# RP2040.net
KiCad netlist of a schematic drawn in Altium Designer
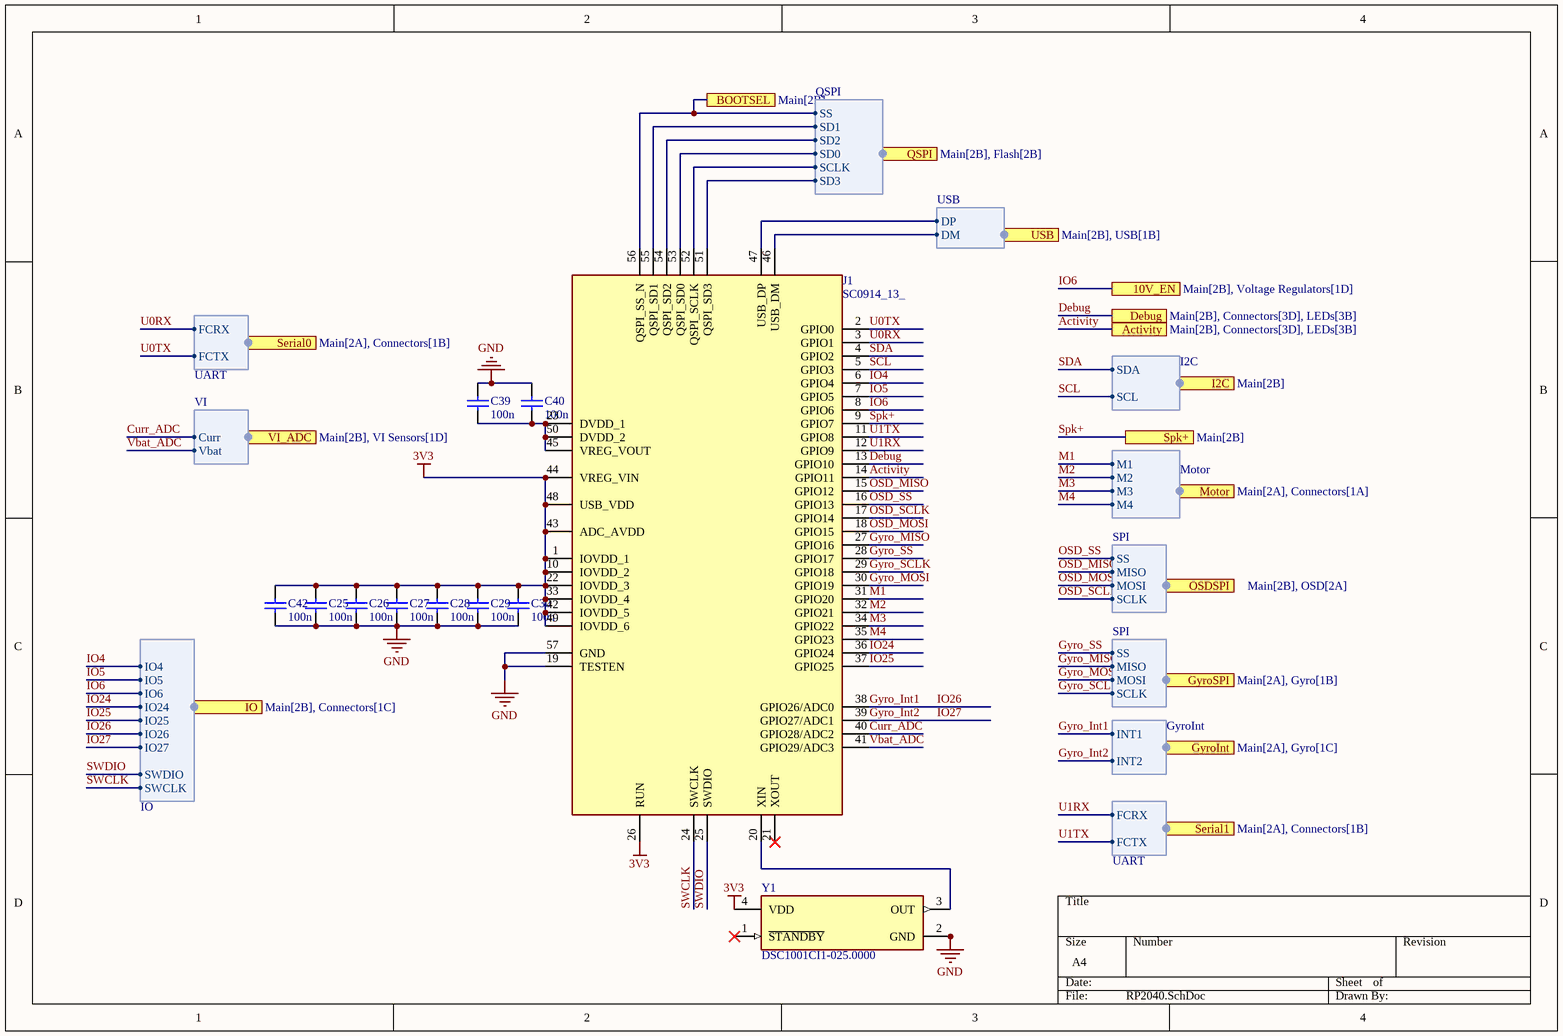
[diagram p0: RP2040.SchDoc]

(export (version "E")
  (design (tool "Eeschema 10.0.6"))
  (components
    (comp (ref "C25")
      (value "100n")
      (footprint "CAPC0603(1608)55_N")
      (description "Keramikvielschichtkondensator, SMD, Baureihe MC, ± 20%")
      (fields (field (name "MANUFACTURER") "Multicomp"))
      (libsource (lib "Standardbauteile") (part "Cap 100n"))
    )
    (comp (ref "C26")
      (value "100n")
      (footprint "CAPC0603(1608)55_N")
      (description "Keramikvielschichtkondensator, SMD, Baureihe MC, ± 20%")
      (fields (field (name "MANUFACTURER") "Multicomp"))
      (libsource (lib "Standardbauteile") (part "Cap 100n"))
    )
    (comp (ref "C27")
      (value "100n")
      (footprint "CAPC0603(1608)55_N")
      (description "Keramikvielschichtkondensator, SMD, Baureihe MC, ± 20%")
      (fields (field (name "MANUFACTURER") "Multicomp"))
      (libsource (lib "Standardbauteile") (part "Cap 100n"))
    )
    (comp (ref "C28")
      (value "100n")
      (footprint "CAPC0603(1608)55_N")
      (description "Keramikvielschichtkondensator, SMD, Baureihe MC, ± 20%")
      (fields (field (name "MANUFACTURER") "Multicomp"))
      (libsource (lib "Standardbauteile") (part "Cap 100n"))
    )
    (comp (ref "C29")
      (value "100n")
      (footprint "CAPC0603(1608)55_N")
      (description "Keramikvielschichtkondensator, SMD, Baureihe MC, ± 20%")
      (fields (field (name "MANUFACTURER") "Multicomp"))
      (libsource (lib "Standardbauteile") (part "Cap 100n"))
    )
    (comp (ref "C30")
      (value "100n")
      (footprint "CAPC0603(1608)55_N")
      (description "Keramikvielschichtkondensator, SMD, Baureihe MC, ± 20%")
      (fields (field (name "MANUFACTURER") "Multicomp"))
      (libsource (lib "Standardbauteile") (part "Cap 100n"))
    )
    (comp (ref "C39")
      (value "100n")
      (footprint "CAPC0603(1608)55_N")
      (description "Keramikvielschichtkondensator, SMD, Baureihe MC, ± 20%")
      (fields (field (name "MANUFACTURER") "Multicomp"))
      (libsource (lib "Standardbauteile") (part "Cap 100n"))
    )
    (comp (ref "C40")
      (value "100n")
      (footprint "CAPC0603(1608)55_N")
      (description "Keramikvielschichtkondensator, SMD, Baureihe MC, ± 20%")
      (fields (field (name "MANUFACTURER") "Multicomp"))
      (libsource (lib "Standardbauteile") (part "Cap 100n"))
    )
    (comp (ref "C42")
      (value "100n")
      (footprint "CAPC0603(1608)55_N")
      (description "Keramikvielschichtkondensator, SMD, Baureihe MC, ± 20%")
      (fields (field (name "MANUFACTURER") "Multicomp"))
      (libsource (lib "Standardbauteile") (part "Cap 100n"))
    )
    (comp (ref "J1")
      (value "SC0914_13_")
      (footprint "Custom Components:SC091413")
      (description "Connector")
      (fields
        (field (name "MANUFACTURER_PART_NUMBER") "SC0914(13)")
        (field (name "MOUSER PART NUMBER") "358-SC091413")
      )
      (libsource (lib "Custom Components") (part "SC0914_13_"))
    )
    (comp (ref "Y1")
      (value "DSC1001CI1-025.0000")
      (footprint "FP-CDFN3225-4LD-PL-1-MFG")
      (description "MEMS OSC XO 25.0000MHZ CMOS SMD")
      (libsource (lib "Altium Content Vault") (part "8720c5899389794f50cb41edc4e4c8a"))
    )
  )
  (nets
    (net (code "10") (name "/Activity") (class "Default")
      (node (ref "J1") (pin "14") (pinfunction "GPIO11_14") (pintype "passive"))
    )
    (net (code "11") (name "/BOOTSEL") (class "Default")
      (node (ref "J1") (pin "56") (pinfunction "QSPI_SS_N_56") (pintype "passive"))
    )
    (net (code "12") (name "/Curr_ADC") (class "Default")
      (node (ref "J1") (pin "40") (pinfunction "GPIO28/ADC2_40") (pintype "passive"))
    )
    (net (code "13") (name "/DM") (class "Default")
      (node (ref "J1") (pin "46") (pinfunction "USB_DM_46") (pintype "passive"))
    )
    (net (code "14") (name "/DP") (class "Default")
      (node (ref "J1") (pin "47") (pinfunction "USB_DP_47") (pintype "passive"))
    )
    (net (code "15") (name "/Debug") (class "Default")
      (node (ref "J1") (pin "13") (pinfunction "GPIO10_13") (pintype "passive"))
    )
    (net (code "16") (name "/Gyro_Int1") (class "Default")
      (node (ref "J1") (pin "38") (pinfunction "GPIO26/ADC0_38") (pintype "passive"))
    )
    (net (code "17") (name "/Gyro_Int2") (class "Default")
      (node (ref "J1") (pin "39") (pinfunction "GPIO27/ADC1_39") (pintype "passive"))
    )
    (net (code "18") (name "/Gyro_MISO") (class "Default")
      (node (ref "J1") (pin "27") (pinfunction "GPIO16_27") (pintype "passive"))
    )
    (net (code "19") (name "/Gyro_MOSI") (class "Default")
      (node (ref "J1") (pin "30") (pinfunction "GPIO19_30") (pintype "passive"))
    )
    (net (code "20") (name "/Gyro_SCLK") (class "Default")
      (node (ref "J1") (pin "29") (pinfunction "GPIO18_29") (pintype "passive"))
    )
    (net (code "21") (name "/Gyro_SS") (class "Default")
      (node (ref "J1") (pin "28") (pinfunction "GPIO17_28") (pintype "passive"))
    )
    (net (code "22") (name "/IO4") (class "Default")
      (node (ref "J1") (pin "6") (pinfunction "GPIO4_6") (pintype "passive"))
    )
    (net (code "23") (name "/IO5") (class "Default")
      (node (ref "J1") (pin "7") (pinfunction "GPIO5_7") (pintype "passive"))
    )
    (net (code "24") (name "/IO6") (class "Default")
      (node (ref "J1") (pin "8") (pinfunction "GPIO6_8") (pintype "passive"))
    )
    (net (code "25") (name "/IO24") (class "Default")
      (node (ref "J1") (pin "36") (pinfunction "GPIO24_36") (pintype "passive"))
    )
    (net (code "26") (name "/IO25") (class "Default")
      (node (ref "J1") (pin "37") (pinfunction "GPIO25_37") (pintype "passive"))
    )
    (net (code "27") (name "/M1") (class "Default")
      (node (ref "J1") (pin "31") (pinfunction "GPIO20_31") (pintype "passive"))
    )
    (net (code "28") (name "/M2") (class "Default")
      (node (ref "J1") (pin "32") (pinfunction "GPIO21_32") (pintype "passive"))
    )
    (net (code "29") (name "/M3") (class "Default")
      (node (ref "J1") (pin "34") (pinfunction "GPIO22_34") (pintype "passive"))
    )
    (net (code "30") (name "/M4") (class "Default")
      (node (ref "J1") (pin "35") (pinfunction "GPIO23_35") (pintype "passive"))
    )
    (net (code "31") (name "/OSD_MISO") (class "Default")
      (node (ref "J1") (pin "15") (pinfunction "GPIO12_15") (pintype "passive"))
    )
    (net (code "32") (name "/OSD_MOSI") (class "Default")
      (node (ref "J1") (pin "18") (pinfunction "GPIO15_18") (pintype "passive"))
    )
    (net (code "33") (name "/OSD_SCLK") (class "Default")
      (node (ref "J1") (pin "17") (pinfunction "GPIO14_17") (pintype "passive"))
    )
    (net (code "34") (name "/OSD_SS") (class "Default")
      (node (ref "J1") (pin "16") (pinfunction "GPIO13_16") (pintype "passive"))
    )
    (net (code "35") (name "/SCL") (class "Default")
      (node (ref "J1") (pin "5") (pinfunction "GPIO3_5") (pintype "passive"))
    )
    (net (code "36") (name "/SD0") (class "Default")
      (node (ref "J1") (pin "53") (pinfunction "QSPI_SD0_53") (pintype "passive"))
    )
    (net (code "37") (name "/SD1") (class "Default")
      (node (ref "J1") (pin "55") (pinfunction "QSPI_SD1_55") (pintype "passive"))
    )
    (net (code "38") (name "/SD2") (class "Default")
      (node (ref "J1") (pin "54") (pinfunction "QSPI_SD2_54") (pintype "passive"))
    )
    (net (code "39") (name "/SD3") (class "Default")
      (node (ref "J1") (pin "51") (pinfunction "QSPI_SD3_51") (pintype "passive"))
    )
    (net (code "40") (name "/SDA") (class "Default")
      (node (ref "J1") (pin "4") (pinfunction "GPIO2_4") (pintype "passive"))
    )
    (net (code "41") (name "/SWCLK") (class "Default")
      (node (ref "J1") (pin "24") (pinfunction "SWCLK_24") (pintype "passive"))
    )
    (net (code "42") (name "/SWDIO") (class "Default")
      (node (ref "J1") (pin "25") (pinfunction "SWDIO_25") (pintype "passive"))
    )
    (net (code "43") (name "/Spk+") (class "Default")
      (node (ref "J1") (pin "9") (pinfunction "GPIO7_9") (pintype "passive"))
    )
    (net (code "44") (name "/U0RX") (class "Default")
      (node (ref "J1") (pin "3") (pinfunction "GPIO1_3") (pintype "passive"))
    )
    (net (code "45") (name "/U0TX") (class "Default")
      (node (ref "J1") (pin "2") (pinfunction "GPIO0_2") (pintype "passive"))
    )
    (net (code "46") (name "/U1RX") (class "Default")
      (node (ref "J1") (pin "12") (pinfunction "GPIO9_12") (pintype "passive"))
    )
    (net (code "47") (name "/U1TX") (class "Default")
      (node (ref "J1") (pin "11") (pinfunction "GPIO8_11") (pintype "passive"))
    )
    (net (code "48") (name "/Vbat_ADC") (class "Default")
      (node (ref "J1") (pin "41") (pinfunction "GPIO29/ADC3_41") (pintype "passive"))
    )
    (net (code "58") (name "3V3") (class "Default")
      (node (ref "C25") (pin "2") (pinfunction "2_2") (pintype "passive"))
      (node (ref "C26") (pin "2") (pinfunction "2_2") (pintype "passive"))
      (node (ref "C27") (pin "2") (pinfunction "2_2") (pintype "passive"))
      (node (ref "C28") (pin "2") (pinfunction "2_2") (pintype "passive"))
      (node (ref "C29") (pin "2") (pinfunction "2_2") (pintype "passive"))
      (node (ref "C30") (pin "2") (pinfunction "2_2") (pintype "passive"))
      (node (ref "C42") (pin "2") (pinfunction "2_2") (pintype "passive"))
      (node (ref "J1") (pin "1") (pinfunction "IOVDD_1_1") (pintype "passive"))
      (node (ref "J1") (pin "10") (pinfunction "IOVDD_2_10") (pintype "passive"))
      (node (ref "J1") (pin "22") (pinfunction "IOVDD_3_22") (pintype "passive"))
      (node (ref "J1") (pin "26") (pinfunction "RUN_26") (pintype "passive"))
      (node (ref "J1") (pin "33") (pinfunction "IOVDD_4_33") (pintype "passive"))
      (node (ref "J1") (pin "42") (pinfunction "IOVDD_5_42") (pintype "passive"))
      (node (ref "J1") (pin "43") (pinfunction "ADC_AVDD_43") (pintype "passive"))
      (node (ref "J1") (pin "44") (pinfunction "VREG_VIN_44") (pintype "passive"))
      (node (ref "J1") (pin "48") (pinfunction "USB_VDD_48") (pintype "passive"))
      (node (ref "J1") (pin "49") (pinfunction "IOVDD_6_49") (pintype "passive"))
      (node (ref "Y1") (pin "4") (pinfunction "VDD_4") (pintype "power_in"))
    )
    (net (code "59") (name "GND") (class "Default")
      (node (ref "C25") (pin "1") (pinfunction "1_1") (pintype "passive"))
      (node (ref "C26") (pin "1") (pinfunction "1_1") (pintype "passive"))
      (node (ref "C27") (pin "1") (pinfunction "1_1") (pintype "passive"))
      (node (ref "C28") (pin "1") (pinfunction "1_1") (pintype "passive"))
      (node (ref "C29") (pin "1") (pinfunction "1_1") (pintype "passive"))
      (node (ref "C30") (pin "1") (pinfunction "1_1") (pintype "passive"))
      (node (ref "C39") (pin "2") (pinfunction "2_2") (pintype "passive"))
      (node (ref "C40") (pin "2") (pinfunction "2_2") (pintype "passive"))
      (node (ref "C42") (pin "1") (pinfunction "1_1") (pintype "passive"))
      (node (ref "J1") (pin "19") (pinfunction "TESTEN_19") (pintype "passive"))
      (node (ref "J1") (pin "57") (pinfunction "GND_57") (pintype "passive"))
      (node (ref "Y1") (pin "2") (pinfunction "GND_2") (pintype "power_in"))
    )
    (net (code "60") (name "Net-(J1-DVDD_1)") (class "Default")
      (node (ref "C39") (pin "1") (pinfunction "1_1") (pintype "passive"))
      (node (ref "C40") (pin "1") (pinfunction "1_1") (pintype "passive"))
      (node (ref "J1") (pin "23") (pinfunction "DVDD_1_23") (pintype "passive"))
      (node (ref "J1") (pin "45") (pinfunction "VREG_VOUT_45") (pintype "passive"))
      (node (ref "J1") (pin "50") (pinfunction "DVDD_2_50") (pintype "passive"))
    )
    (net (code "61") (name "Net-(J1-XIN)") (class "Default")
      (node (ref "J1") (pin "20") (pinfunction "XIN_20") (pintype "passive"))
      (node (ref "Y1") (pin "3") (pinfunction "OUT_3") (pintype "output"))
    )
    (net (code "62") (name "unconnected-(J1-QSPI_SCLK-Pad52)") (class "Default")
      (node (ref "J1") (pin "52") (pinfunction "QSPI_SCLK_52") (pintype "passive"))
    )
    (net (code "63") (name "unconnected-(J1-XOUT-Pad21)") (class "Default")
      (node (ref "J1") (pin "21") (pinfunction "XOUT_21") (pintype "passive+no_connect"))
    )
    (net (code "64") (name "unconnected-(Y1-~{STANDBY}-Pad1)") (class "Default")
      (node (ref "Y1") (pin "1") (pinfunction "~{STANDBY}_1") (pintype "input+no_connect"))
    )
  )
)
